# sheet.net
KiCad netlist of a schematic drawn in EAGLE
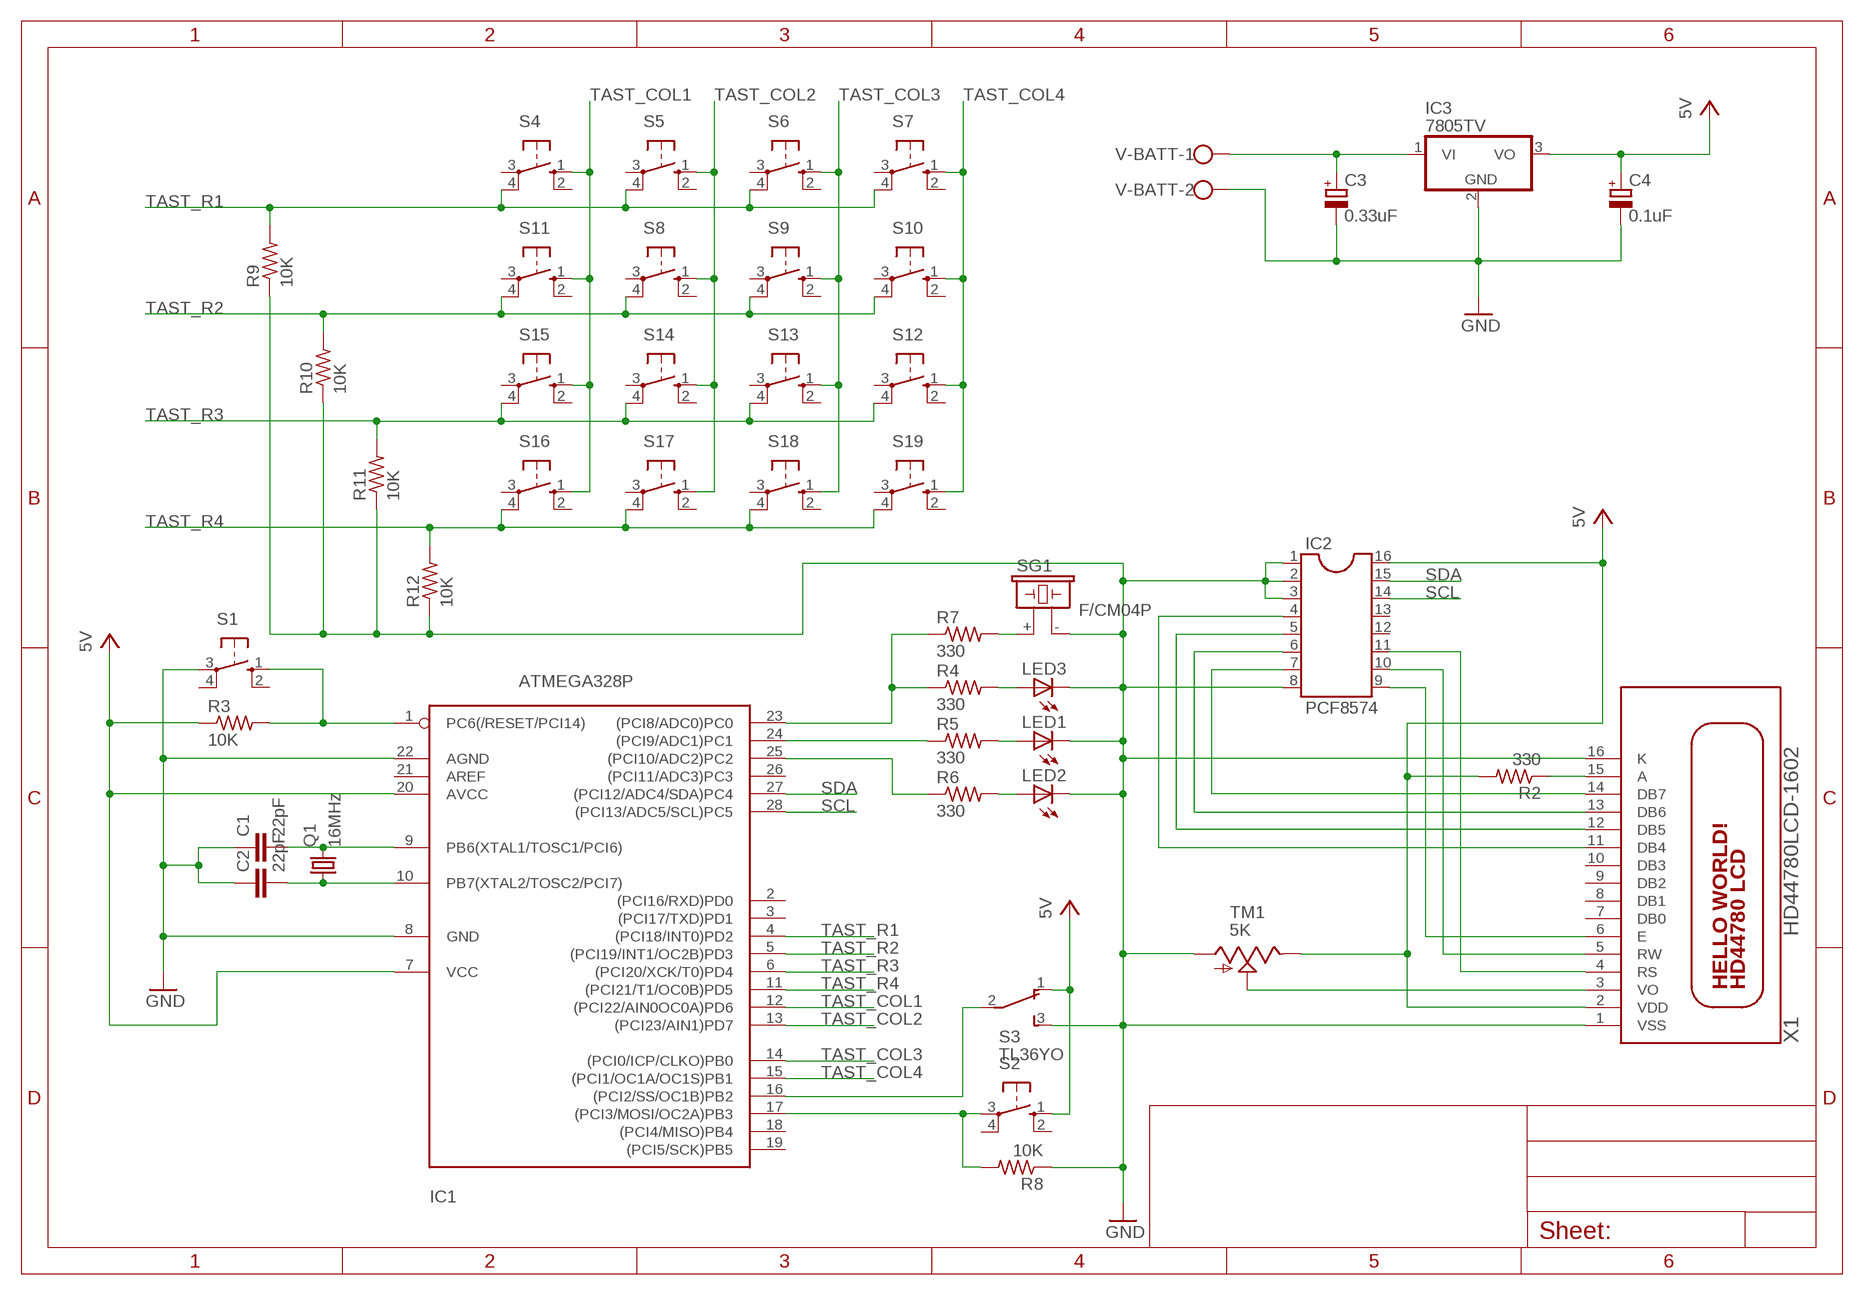
[diagram p0: schematic, sheet 1]

(export (version "E")
  (design (tool "Eeschema 10.0.6"))
  (components
    (comp (ref "C1")
      (value "22pF")
      (footprint "eagle-import:C025-024X044")
      (libsource (lib "eagle-import") (part "C-EU025-024X044"))
    )
    (comp (ref "C2")
      (value "22pF")
      (footprint "eagle-import:C025-024X044")
      (libsource (lib "eagle-import") (part "C-EU025-024X044"))
    )
    (comp (ref "C3")
      (value "0.33uF")
      (footprint "eagle-import:E5-6")
      (libsource (lib "eagle-import") (part "CPOL-EUE5-6"))
    )
    (comp (ref "C4")
      (value "0.1uF")
      (footprint "eagle-import:E5-6")
      (libsource (lib "eagle-import") (part "CPOL-EUE5-6"))
    )
    (comp (ref "FRAME1")
      (value "A4L-LOC")
      (footprint "eagle-import:A4L-LOC")
      (fields
        (field (name "DATE") "23/03/2015")
        (field (name "PAGES") "1/1")
        (field (name "REV") "V1.0")
        (field (name "SHEET_NAME") "Soft Bomb")
      )
      (libsource (lib "eagle-import") (part "A4L-LOC"))
    )
    (comp (ref "IC1")
      (value "ATMEGA328P")
      (footprint "eagle-import:DIL28-3")
      (libsource (lib "eagle-import") (part "ATMEGA168P-20"))
    )
    (comp (ref "IC2")
      (value "PCF8574")
      (footprint "eagle-import:DIL16")
      (libsource (lib "eagle-import") (part "DIL16"))
    )
    (comp (ref "IC3")
      (value "7805TV")
      (footprint "eagle-import:TO220V")
      (libsource (lib "eagle-import") (part "78TV05"))
    )
    (comp (ref "LED1")
      (value "LED5MM")
      (footprint "eagle-import:LED5MM")
      (libsource (lib "eagle-import") (part "LED5MM"))
    )
    (comp (ref "LED2")
      (value "LED3MM")
      (footprint "eagle-import:LED3MM")
      (libsource (lib "eagle-import") (part "LED3MM"))
    )
    (comp (ref "LED3")
      (value "LED3MM")
      (footprint "eagle-import:LED3MM")
      (libsource (lib "eagle-import") (part "LED3MM"))
    )
    (comp (ref "Q1")
      (value "16MHz")
      (footprint "eagle-import:HC49_S")
      (libsource (lib "eagle-import") (part "CRYSTALHC49S"))
    )
    (comp (ref "R2")
      (value "330")
      (footprint "eagle-import:0204_7")
      (libsource (lib "eagle-import") (part "R-US_0204/7"))
    )
    (comp (ref "R3")
      (value "10K")
      (footprint "eagle-import:0207_12")
      (libsource (lib "eagle-import") (part "resistor_R-US_0207/12"))
    )
    (comp (ref "R4")
      (value "330")
      (footprint "eagle-import:0207_12")
      (libsource (lib "eagle-import") (part "resistor_R-US_0207/12"))
    )
    (comp (ref "R5")
      (value "330")
      (footprint "eagle-import:0207_12")
      (libsource (lib "eagle-import") (part "resistor_R-US_0207/12"))
    )
    (comp (ref "R6")
      (value "330")
      (footprint "eagle-import:0207_12")
      (libsource (lib "eagle-import") (part "resistor_R-US_0207/12"))
    )
    (comp (ref "R7")
      (value "330")
      (footprint "eagle-import:0207_12")
      (libsource (lib "eagle-import") (part "resistor_R-US_0207/12"))
    )
    (comp (ref "R8")
      (value "10K")
      (footprint "eagle-import:0207_12")
      (libsource (lib "eagle-import") (part "resistor_R-US_0207/12"))
    )
    (comp (ref "R9")
      (value "10K")
      (footprint "eagle-import:0207_12")
      (libsource (lib "eagle-import") (part "resistor_R-US_0207/12"))
    )
    (comp (ref "R10")
      (value "10K")
      (footprint "eagle-import:0207_12")
      (libsource (lib "eagle-import") (part "resistor_R-US_0207/12"))
    )
    (comp (ref "R11")
      (value "10K")
      (footprint "eagle-import:0207_12")
      (libsource (lib "eagle-import") (part "resistor_R-US_0207/12"))
    )
    (comp (ref "R12")
      (value "10K")
      (footprint "eagle-import:0207_12")
      (libsource (lib "eagle-import") (part "resistor_R-US_0207/12"))
    )
    (comp (ref "S1")
      (value "40-XX")
      (footprint "eagle-import:B3F-40XX")
      (fields (field (name "MF") "OMRON COMPONENTS USA") (field (name "MPN") "B3F-4000"))
      (libsource (lib "eagle-import") (part "40-XX"))
    )
    (comp (ref "S2")
      (value "40-XX")
      (footprint "eagle-import:B3F-40XX")
      (fields (field (name "MF") "OMRON COMPONENTS USA") (field (name "MPN") "B3F-4000"))
      (libsource (lib "eagle-import") (part "40-XX"))
    )
    (comp (ref "S3")
      (value "TL36YO")
      (footprint "eagle-import:TL3XYO")
      (libsource (lib "eagle-import") (part "TL36YO"))
    )
    (comp (ref "S4")
      (value "40-XX")
      (footprint "eagle-import:B3F-40XX")
      (fields (field (name "MF") "OMRON COMPONENTS USA") (field (name "MPN") "B3F-4000"))
      (libsource (lib "eagle-import") (part "40-XX"))
    )
    (comp (ref "S5")
      (value "40-XX")
      (footprint "eagle-import:B3F-40XX")
      (fields (field (name "MF") "OMRON COMPONENTS USA") (field (name "MPN") "B3F-4000"))
      (libsource (lib "eagle-import") (part "40-XX"))
    )
    (comp (ref "S6")
      (value "40-XX")
      (footprint "eagle-import:B3F-40XX")
      (fields (field (name "MF") "OMRON COMPONENTS USA") (field (name "MPN") "B3F-4000"))
      (libsource (lib "eagle-import") (part "40-XX"))
    )
    (comp (ref "S7")
      (value "40-XX")
      (footprint "eagle-import:B3F-40XX")
      (fields (field (name "MF") "OMRON COMPONENTS USA") (field (name "MPN") "B3F-4000"))
      (libsource (lib "eagle-import") (part "40-XX"))
    )
    (comp (ref "S8")
      (value "40-XX")
      (footprint "eagle-import:B3F-40XX")
      (fields (field (name "MF") "OMRON COMPONENTS USA") (field (name "MPN") "B3F-4000"))
      (libsource (lib "eagle-import") (part "40-XX"))
    )
    (comp (ref "S9")
      (value "40-XX")
      (footprint "eagle-import:B3F-40XX")
      (fields (field (name "MF") "OMRON COMPONENTS USA") (field (name "MPN") "B3F-4000"))
      (libsource (lib "eagle-import") (part "40-XX"))
    )
    (comp (ref "S10")
      (value "40-XX")
      (footprint "eagle-import:B3F-40XX")
      (fields (field (name "MF") "OMRON COMPONENTS USA") (field (name "MPN") "B3F-4000"))
      (libsource (lib "eagle-import") (part "40-XX"))
    )
    (comp (ref "S11")
      (value "40-XX")
      (footprint "eagle-import:B3F-40XX")
      (fields (field (name "MF") "OMRON COMPONENTS USA") (field (name "MPN") "B3F-4000"))
      (libsource (lib "eagle-import") (part "40-XX"))
    )
    (comp (ref "S12")
      (value "40-XX")
      (footprint "eagle-import:B3F-40XX")
      (fields (field (name "MF") "OMRON COMPONENTS USA") (field (name "MPN") "B3F-4000"))
      (libsource (lib "eagle-import") (part "40-XX"))
    )
    (comp (ref "S13")
      (value "40-XX")
      (footprint "eagle-import:B3F-40XX")
      (fields (field (name "MF") "OMRON COMPONENTS USA") (field (name "MPN") "B3F-4000"))
      (libsource (lib "eagle-import") (part "40-XX"))
    )
    (comp (ref "S14")
      (value "40-XX")
      (footprint "eagle-import:B3F-40XX")
      (fields (field (name "MF") "OMRON COMPONENTS USA") (field (name "MPN") "B3F-4000"))
      (libsource (lib "eagle-import") (part "40-XX"))
    )
    (comp (ref "S15")
      (value "40-XX")
      (footprint "eagle-import:B3F-40XX")
      (fields (field (name "MF") "OMRON COMPONENTS USA") (field (name "MPN") "B3F-4000"))
      (libsource (lib "eagle-import") (part "40-XX"))
    )
    (comp (ref "S16")
      (value "40-XX")
      (footprint "eagle-import:B3F-40XX")
      (fields (field (name "MF") "OMRON COMPONENTS USA") (field (name "MPN") "B3F-4000"))
      (libsource (lib "eagle-import") (part "40-XX"))
    )
    (comp (ref "S17")
      (value "40-XX")
      (footprint "eagle-import:B3F-40XX")
      (fields (field (name "MF") "OMRON COMPONENTS USA") (field (name "MPN") "B3F-4000"))
      (libsource (lib "eagle-import") (part "40-XX"))
    )
    (comp (ref "S18")
      (value "40-XX")
      (footprint "eagle-import:B3F-40XX")
      (fields (field (name "MF") "OMRON COMPONENTS USA") (field (name "MPN") "B3F-4000"))
      (libsource (lib "eagle-import") (part "40-XX"))
    )
    (comp (ref "S19")
      (value "40-XX")
      (footprint "eagle-import:B3F-40XX")
      (fields (field (name "MF") "OMRON COMPONENTS USA") (field (name "MPN") "B3F-4000"))
      (libsource (lib "eagle-import") (part "40-XX"))
    )
    (comp (ref "SG1")
      (value "F/CM04P")
      (footprint "eagle-import:F_CM04P")
      (libsource (lib "eagle-import") (part "F/CM04P"))
    )
    (comp (ref "TM1")
      (value "5K")
      (footprint "eagle-import:6MM")
      (libsource (lib "eagle-import") (part "TRIM"))
    )
    (comp (ref "V-BATT")
      (value "W237-102")
      (footprint "eagle-import:W237-102")
      (fields (field (name "MPN") "237-102"))
      (libsource (lib "eagle-import") (part "W237-102"))
    )
    (comp (ref "X1")
      (value "HD44780LCD-1602")
      (footprint "eagle-import:LCD1602")
      (libsource (lib "eagle-import") (part "HD44780LCD-1602"))
    )
  )
  (nets
    (net (code "1") (name "/SCL") (class "Default")
      (node (ref "IC1") (pin "28") (pinfunction "(PCI13/ADC5/SCL)PC5_28") (pintype "bidirectional"))
      (node (ref "IC2") (pin "14") (pinfunction "14_14") (pintype "passive"))
    )
    (net (code "2") (name "/SDA") (class "Default")
      (node (ref "IC1") (pin "27") (pinfunction "(PCI12/ADC4/SDA)PC4_27") (pintype "bidirectional"))
      (node (ref "IC2") (pin "15") (pinfunction "15_15") (pintype "passive"))
    )
    (net (code "3") (name "/TAST_COL1") (class "Default")
      (node (ref "IC1") (pin "12") (pinfunction "(PCI22/AIN0OC0A)PD6_12") (pintype "bidirectional"))
      (node (ref "S11") (pin "1") (pinfunction "S_1") (pintype "passive"))
      (node (ref "S15") (pin "1") (pinfunction "S_1") (pintype "passive"))
      (node (ref "S16") (pin "1") (pinfunction "S_1") (pintype "passive"))
      (node (ref "S4") (pin "1") (pinfunction "S_1") (pintype "passive"))
    )
    (net (code "4") (name "/TAST_COL2") (class "Default")
      (node (ref "IC1") (pin "13") (pinfunction "(PCI23/AIN1)PD7_13") (pintype "bidirectional"))
      (node (ref "S14") (pin "1") (pinfunction "S_1") (pintype "passive"))
      (node (ref "S17") (pin "1") (pinfunction "S_1") (pintype "passive"))
      (node (ref "S5") (pin "1") (pinfunction "S_1") (pintype "passive"))
      (node (ref "S8") (pin "1") (pinfunction "S_1") (pintype "passive"))
    )
    (net (code "5") (name "/TAST_COL3") (class "Default")
      (node (ref "IC1") (pin "14") (pinfunction "(PCI0/ICP/CLKO)PB0_14") (pintype "bidirectional"))
      (node (ref "S13") (pin "1") (pinfunction "S_1") (pintype "passive"))
      (node (ref "S18") (pin "1") (pinfunction "S_1") (pintype "passive"))
      (node (ref "S6") (pin "1") (pinfunction "S_1") (pintype "passive"))
      (node (ref "S9") (pin "1") (pinfunction "S_1") (pintype "passive"))
    )
    (net (code "6") (name "/TAST_COL4") (class "Default")
      (node (ref "IC1") (pin "15") (pinfunction "(PCI1/OC1A/OC1S)PB1_15") (pintype "bidirectional"))
      (node (ref "S10") (pin "1") (pinfunction "S_1") (pintype "passive"))
      (node (ref "S12") (pin "1") (pinfunction "S_1") (pintype "passive"))
      (node (ref "S19") (pin "1") (pinfunction "S_1") (pintype "passive"))
      (node (ref "S7") (pin "1") (pinfunction "S_1") (pintype "passive"))
    )
    (net (code "7") (name "/TAST_R1") (class "Default")
      (node (ref "IC1") (pin "4") (pinfunction "(PCI18/INT0)PD2_4") (pintype "bidirectional"))
      (node (ref "R9") (pin "2") (pinfunction "2_2") (pintype "passive"))
      (node (ref "S4") (pin "4") (pinfunction "P1_4") (pintype "passive"))
      (node (ref "S5") (pin "4") (pinfunction "P1_4") (pintype "passive"))
      (node (ref "S6") (pin "4") (pinfunction "P1_4") (pintype "passive"))
      (node (ref "S7") (pin "4") (pinfunction "P1_4") (pintype "passive"))
    )
    (net (code "8") (name "/TAST_R2") (class "Default")
      (node (ref "IC1") (pin "5") (pinfunction "(PCI19/INT1/OC2B)PD3_5") (pintype "bidirectional"))
      (node (ref "R10") (pin "2") (pinfunction "2_2") (pintype "passive"))
      (node (ref "S10") (pin "4") (pinfunction "P1_4") (pintype "passive"))
      (node (ref "S11") (pin "4") (pinfunction "P1_4") (pintype "passive"))
      (node (ref "S8") (pin "4") (pinfunction "P1_4") (pintype "passive"))
      (node (ref "S9") (pin "4") (pinfunction "P1_4") (pintype "passive"))
    )
    (net (code "9") (name "/TAST_R3") (class "Default")
      (node (ref "IC1") (pin "6") (pinfunction "(PCI20/XCK/T0)PD4_6") (pintype "bidirectional"))
      (node (ref "R11") (pin "2") (pinfunction "2_2") (pintype "passive"))
      (node (ref "S12") (pin "4") (pinfunction "P1_4") (pintype "passive"))
      (node (ref "S13") (pin "4") (pinfunction "P1_4") (pintype "passive"))
      (node (ref "S14") (pin "4") (pinfunction "P1_4") (pintype "passive"))
      (node (ref "S15") (pin "4") (pinfunction "P1_4") (pintype "passive"))
    )
    (net (code "10") (name "/TAST_R4") (class "Default")
      (node (ref "IC1") (pin "11") (pinfunction "(PCI21/T1/OC0B)PD5_11") (pintype "bidirectional"))
      (node (ref "R12") (pin "2") (pinfunction "2_2") (pintype "passive"))
      (node (ref "S16") (pin "4") (pinfunction "P1_4") (pintype "passive"))
      (node (ref "S17") (pin "4") (pinfunction "P1_4") (pintype "passive"))
      (node (ref "S18") (pin "4") (pinfunction "P1_4") (pintype "passive"))
      (node (ref "S19") (pin "4") (pinfunction "P1_4") (pintype "passive"))
    )
    (net (code "11") (name "5V") (class "Default")
      (node (ref "C4") (pin "+") (pinfunction "+_+") (pintype "passive"))
      (node (ref "IC1") (pin "20") (pinfunction "AVCC_20") (pintype "bidirectional"))
      (node (ref "IC1") (pin "7") (pinfunction "VCC_7") (pintype "bidirectional"))
      (node (ref "IC2") (pin "16") (pinfunction "16_16") (pintype "passive"))
      (node (ref "IC3") (pin "3") (pinfunction "VO_3") (pintype "passive"))
      (node (ref "R2") (pin "2") (pinfunction "2_2") (pintype "passive"))
      (node (ref "R3") (pin "1") (pinfunction "1_1") (pintype "passive"))
      (node (ref "S2") (pin "1") (pinfunction "S_1") (pintype "passive"))
      (node (ref "S3") (pin "1") (pinfunction "O_1") (pintype "passive"))
      (node (ref "TM1") (pin "E") (pinfunction "E_E") (pintype "passive"))
      (node (ref "X1") (pin "2") (pinfunction "VDD_2") (pintype "power_in"))
    )
    (net (code "12") (name "GND") (class "Default")
      (node (ref "C1") (pin "1") (pinfunction "1_1") (pintype "passive"))
      (node (ref "C2") (pin "1") (pinfunction "1_1") (pintype "passive"))
      (node (ref "C3") (pin "-") (pinfunction "-_-") (pintype "passive"))
      (node (ref "C4") (pin "-") (pinfunction "-_-") (pintype "passive"))
      (node (ref "IC1") (pin "22") (pinfunction "AGND_22") (pintype "bidirectional"))
      (node (ref "IC1") (pin "8") (pinfunction "GND_8") (pintype "bidirectional"))
      (node (ref "IC2") (pin "1") (pinfunction "1_1") (pintype "passive"))
      (node (ref "IC2") (pin "2") (pinfunction "2_2") (pintype "passive"))
      (node (ref "IC2") (pin "3") (pinfunction "3_3") (pintype "passive"))
      (node (ref "IC2") (pin "8") (pinfunction "8_8") (pintype "passive"))
      (node (ref "IC3") (pin "2") (pinfunction "GND_2") (pintype "passive"))
      (node (ref "LED1") (pin "K") (pinfunction "C_K") (pintype "passive"))
      (node (ref "LED2") (pin "K") (pinfunction "C_K") (pintype "passive"))
      (node (ref "LED3") (pin "K") (pinfunction "C_K") (pintype "passive"))
      (node (ref "R10") (pin "1") (pinfunction "1_1") (pintype "passive"))
      (node (ref "R11") (pin "1") (pinfunction "1_1") (pintype "passive"))
      (node (ref "R12") (pin "1") (pinfunction "1_1") (pintype "passive"))
      (node (ref "R8") (pin "1") (pinfunction "1_1") (pintype "passive"))
      (node (ref "R9") (pin "1") (pinfunction "1_1") (pintype "passive"))
      (node (ref "S1") (pin "3") (pinfunction "P_3") (pintype "passive"))
      (node (ref "S3") (pin "3") (pinfunction "S_3") (pintype "passive"))
      (node (ref "SG1") (pin "-") (pinfunction "2_-") (pintype "passive"))
      (node (ref "TM1") (pin "A") (pinfunction "A_A") (pintype "passive"))
      (node (ref "V-BATT") (pin "2") (pinfunction "KL_2") (pintype "passive"))
      (node (ref "X1") (pin "1") (pinfunction "VSS_1") (pintype "power_in"))
      (node (ref "X1") (pin "16") (pinfunction "K_16") (pintype "input"))
    )
    (net (code "13") (name "Net-(IC1-(PCI2{slash}SS{slash}OC1B)PB2)") (class "Default")
      (node (ref "IC1") (pin "16") (pinfunction "(PCI2/SS/OC1B)PB2_16") (pintype "bidirectional"))
      (node (ref "S3") (pin "2") (pinfunction "P_2") (pintype "passive"))
    )
    (net (code "14") (name "Net-(IC1-(PCI3{slash}MOSI{slash}OC2A)PB3)") (class "Default")
      (node (ref "IC1") (pin "17") (pinfunction "(PCI3/MOSI/OC2A)PB3_17") (pintype "bidirectional"))
      (node (ref "R8") (pin "2") (pinfunction "2_2") (pintype "passive"))
      (node (ref "S2") (pin "3") (pinfunction "P_3") (pintype "passive"))
    )
    (net (code "15") (name "Net-(IC1-(PCI8{slash}ADC0)PC0)") (class "Default")
      (node (ref "IC1") (pin "23") (pinfunction "(PCI8/ADC0)PC0_23") (pintype "bidirectional"))
      (node (ref "R4") (pin "1") (pinfunction "1_1") (pintype "passive"))
      (node (ref "R7") (pin "1") (pinfunction "1_1") (pintype "passive"))
    )
    (net (code "16") (name "Net-(IC1-(PCI9{slash}ADC1)PC1)") (class "Default")
      (node (ref "IC1") (pin "24") (pinfunction "(PCI9/ADC1)PC1_24") (pintype "bidirectional"))
      (node (ref "R5") (pin "1") (pinfunction "1_1") (pintype "passive"))
    )
    (net (code "17") (name "Net-(IC1-(PCI10{slash}ADC2)PC2)") (class "Default")
      (node (ref "IC1") (pin "25") (pinfunction "(PCI10/ADC2)PC2_25") (pintype "bidirectional"))
      (node (ref "R6") (pin "1") (pinfunction "1_1") (pintype "passive"))
    )
    (net (code "18") (name "Net-(IC1-PB6(XTAL1{slash}TOSC1{slash}PCI6))") (class "Default")
      (node (ref "C1") (pin "2") (pinfunction "2_2") (pintype "passive"))
      (node (ref "IC1") (pin "9") (pinfunction "PB6(XTAL1/TOSC1/PCI6)_9") (pintype "bidirectional"))
      (node (ref "Q1") (pin "2") (pinfunction "2_2") (pintype "passive"))
    )
    (net (code "19") (name "Net-(IC1-PB7(XTAL2{slash}TOSC2{slash}PCI7))") (class "Default")
      (node (ref "C2") (pin "2") (pinfunction "2_2") (pintype "passive"))
      (node (ref "IC1") (pin "10") (pinfunction "PB7(XTAL2/TOSC2/PCI7)_10") (pintype "bidirectional"))
      (node (ref "Q1") (pin "1") (pinfunction "1_1") (pintype "passive"))
    )
    (net (code "20") (name "Net-(IC1-PC6({slash}RESET{slash}PCI14))") (class "Default")
      (node (ref "IC1") (pin "1") (pinfunction "PC6(/RESET/PCI14)_1") (pintype "bidirectional"))
      (node (ref "R3") (pin "2") (pinfunction "2_2") (pintype "passive"))
      (node (ref "S1") (pin "1") (pinfunction "S_1") (pintype "passive"))
    )
    (net (code "21") (name "Net-(IC3-VI)") (class "Default")
      (node (ref "C3") (pin "+") (pinfunction "+_+") (pintype "passive"))
      (node (ref "IC3") (pin "1") (pinfunction "VI_1") (pintype "input"))
      (node (ref "V-BATT") (pin "1") (pinfunction "KL_1") (pintype "passive"))
    )
    (net (code "22") (name "Net-(LED1-PadA)") (class "Default")
      (node (ref "LED1") (pin "A") (pinfunction "A_A") (pintype "passive"))
      (node (ref "R5") (pin "2") (pinfunction "2_2") (pintype "passive"))
    )
    (net (code "23") (name "Net-(LED2-PadA)") (class "Default")
      (node (ref "LED2") (pin "A") (pinfunction "A_A") (pintype "passive"))
      (node (ref "R6") (pin "2") (pinfunction "2_2") (pintype "passive"))
    )
    (net (code "24") (name "Net-(LED3-PadA)") (class "Default")
      (node (ref "LED3") (pin "A") (pinfunction "A_A") (pintype "passive"))
      (node (ref "R4") (pin "2") (pinfunction "2_2") (pintype "passive"))
    )
    (net (code "25") (name "Net-(SG1-1)") (class "Default")
      (node (ref "R7") (pin "2") (pinfunction "2_2") (pintype "passive"))
      (node (ref "SG1") (pin "+") (pinfunction "1_+") (pintype "passive"))
    )
    (net (code "26") (name "Net-(X1-A)") (class "Default")
      (node (ref "R2") (pin "1") (pinfunction "1_1") (pintype "passive"))
      (node (ref "X1") (pin "15") (pinfunction "A_15") (pintype "input"))
    )
    (net (code "27") (name "Net-(X1-DB4)") (class "Default")
      (node (ref "IC2") (pin "4") (pinfunction "4_4") (pintype "passive"))
      (node (ref "X1") (pin "11") (pinfunction "DB4_11") (pintype "bidirectional"))
    )
    (net (code "28") (name "Net-(X1-DB5)") (class "Default")
      (node (ref "IC2") (pin "5") (pinfunction "5_5") (pintype "passive"))
      (node (ref "X1") (pin "12") (pinfunction "DB5_12") (pintype "bidirectional"))
    )
    (net (code "29") (name "Net-(X1-DB6)") (class "Default")
      (node (ref "IC2") (pin "6") (pinfunction "6_6") (pintype "passive"))
      (node (ref "X1") (pin "13") (pinfunction "DB6_13") (pintype "bidirectional"))
    )
    (net (code "30") (name "Net-(X1-DB7)") (class "Default")
      (node (ref "IC2") (pin "7") (pinfunction "7_7") (pintype "passive"))
      (node (ref "X1") (pin "14") (pinfunction "DB7_14") (pintype "bidirectional"))
    )
    (net (code "31") (name "Net-(X1-E)") (class "Default")
      (node (ref "IC2") (pin "9") (pinfunction "9_9") (pintype "passive"))
      (node (ref "X1") (pin "6") (pinfunction "E_6") (pintype "input"))
    )
    (net (code "32") (name "Net-(X1-RS)") (class "Default")
      (node (ref "IC2") (pin "11") (pinfunction "11_11") (pintype "passive"))
      (node (ref "X1") (pin "4") (pinfunction "RS_4") (pintype "input"))
    )
    (net (code "33") (name "Net-(X1-RW)") (class "Default")
      (node (ref "IC2") (pin "10") (pinfunction "10_10") (pintype "passive"))
      (node (ref "X1") (pin "5") (pinfunction "RW_5") (pintype "input"))
    )
    (net (code "34") (name "Net-(X1-VO)") (class "Default")
      (node (ref "TM1") (pin "S") (pinfunction "S_S") (pintype "passive"))
      (node (ref "X1") (pin "3") (pinfunction "VO_3") (pintype "input"))
    )
    (net (code "35") (name "unconnected-(IC1-(PCI4{slash}MISO)PB4-Pad18)") (class "Default")
      (node (ref "IC1") (pin "18") (pinfunction "(PCI4/MISO)PB4_18") (pintype "bidirectional"))
    )
    (net (code "36") (name "unconnected-(IC1-(PCI5{slash}SCK)PB5-Pad19)") (class "Default")
      (node (ref "IC1") (pin "19") (pinfunction "(PCI5/SCK)PB5_19") (pintype "bidirectional"))
    )
    (net (code "37") (name "unconnected-(IC1-(PCI11{slash}ADC3)PC3-Pad26)") (class "Default")
      (node (ref "IC1") (pin "26") (pinfunction "(PCI11/ADC3)PC3_26") (pintype "bidirectional"))
    )
    (net (code "38") (name "unconnected-(IC1-(PCI16{slash}RXD)PD0-Pad2)") (class "Default")
      (node (ref "IC1") (pin "2") (pinfunction "(PCI16/RXD)PD0_2") (pintype "bidirectional"))
    )
    (net (code "39") (name "unconnected-(IC1-(PCI17{slash}TXD)PD1-Pad3)") (class "Default")
      (node (ref "IC1") (pin "3") (pinfunction "(PCI17/TXD)PD1_3") (pintype "bidirectional"))
    )
    (net (code "40") (name "unconnected-(IC1-AREF-Pad21)") (class "Default")
      (node (ref "IC1") (pin "21") (pinfunction "AREF_21") (pintype "bidirectional"))
    )
    (net (code "41") (name "unconnected-(IC2-Pad12)") (class "Default")
      (node (ref "IC2") (pin "12") (pinfunction "12_12") (pintype "passive"))
    )
    (net (code "42") (name "unconnected-(IC2-Pad13)") (class "Default")
      (node (ref "IC2") (pin "13") (pinfunction "13_13") (pintype "passive"))
    )
    (net (code "43") (name "unconnected-(S1-P1-Pad4)") (class "Default")
      (node (ref "S1") (pin "4") (pinfunction "P1_4") (pintype "passive"))
    )
    (net (code "44") (name "unconnected-(S1-S1-Pad2)") (class "Default")
      (node (ref "S1") (pin "2") (pinfunction "S1_2") (pintype "passive"))
    )
    (net (code "45") (name "unconnected-(S2-P1-Pad4)") (class "Default")
      (node (ref "S2") (pin "4") (pinfunction "P1_4") (pintype "passive"))
    )
    (net (code "46") (name "unconnected-(S2-S1-Pad2)") (class "Default")
      (node (ref "S2") (pin "2") (pinfunction "S1_2") (pintype "passive"))
    )
    (net (code "47") (name "unconnected-(S4-P-Pad3)") (class "Default")
      (node (ref "S4") (pin "3") (pinfunction "P_3") (pintype "passive"))
    )
    (net (code "48") (name "unconnected-(S4-S1-Pad2)") (class "Default")
      (node (ref "S4") (pin "2") (pinfunction "S1_2") (pintype "passive"))
    )
    (net (code "49") (name "unconnected-(S5-P-Pad3)") (class "Default")
      (node (ref "S5") (pin "3") (pinfunction "P_3") (pintype "passive"))
    )
    (net (code "50") (name "unconnected-(S5-S1-Pad2)") (class "Default")
      (node (ref "S5") (pin "2") (pinfunction "S1_2") (pintype "passive"))
    )
    (net (code "51") (name "unconnected-(S6-P-Pad3)") (class "Default")
      (node (ref "S6") (pin "3") (pinfunction "P_3") (pintype "passive"))
    )
    (net (code "52") (name "unconnected-(S6-S1-Pad2)") (class "Default")
      (node (ref "S6") (pin "2") (pinfunction "S1_2") (pintype "passive"))
    )
    (net (code "53") (name "unconnected-(S7-P-Pad3)") (class "Default")
      (node (ref "S7") (pin "3") (pinfunction "P_3") (pintype "passive"))
    )
    (net (code "54") (name "unconnected-(S7-S1-Pad2)") (class "Default")
      (node (ref "S7") (pin "2") (pinfunction "S1_2") (pintype "passive"))
    )
    (net (code "55") (name "unconnected-(S8-P-Pad3)") (class "Default")
      (node (ref "S8") (pin "3") (pinfunction "P_3") (pintype "passive"))
    )
    (net (code "56") (name "unconnected-(S8-S1-Pad2)") (class "Default")
      (node (ref "S8") (pin "2") (pinfunction "S1_2") (pintype "passive"))
    )
    (net (code "57") (name "unconnected-(S9-P-Pad3)") (class "Default")
      (node (ref "S9") (pin "3") (pinfunction "P_3") (pintype "passive"))
    )
    (net (code "58") (name "unconnected-(S9-S1-Pad2)") (class "Default")
      (node (ref "S9") (pin "2") (pinfunction "S1_2") (pintype "passive"))
    )
    (net (code "59") (name "unconnected-(S10-P-Pad3)") (class "Default")
      (node (ref "S10") (pin "3") (pinfunction "P_3") (pintype "passive"))
    )
    (net (code "60") (name "unconnected-(S10-S1-Pad2)") (class "Default")
      (node (ref "S10") (pin "2") (pinfunction "S1_2") (pintype "passive"))
    )
    (net (code "61") (name "unconnected-(S11-P-Pad3)") (class "Default")
      (node (ref "S11") (pin "3") (pinfunction "P_3") (pintype "passive"))
    )
    (net (code "62") (name "unconnected-(S11-S1-Pad2)") (class "Default")
      (node (ref "S11") (pin "2") (pinfunction "S1_2") (pintype "passive"))
    )
    (net (code "63") (name "unconnected-(S12-P-Pad3)") (class "Default")
      (node (ref "S12") (pin "3") (pinfunction "P_3") (pintype "passive"))
    )
    (net (code "64") (name "unconnected-(S12-S1-Pad2)") (class "Default")
      (node (ref "S12") (pin "2") (pinfunction "S1_2") (pintype "passive"))
    )
    (net (code "65") (name "unconnected-(S13-P-Pad3)") (class "Default")
      (node (ref "S13") (pin "3") (pinfunction "P_3") (pintype "passive"))
    )
    (net (code "66") (name "unconnected-(S13-S1-Pad2)") (class "Default")
      (node (ref "S13") (pin "2") (pinfunction "S1_2") (pintype "passive"))
    )
    (net (code "67") (name "unconnected-(S14-P-Pad3)") (class "Default")
      (node (ref "S14") (pin "3") (pinfunction "P_3") (pintype "passive"))
    )
    (net (code "68") (name "unconnected-(S14-S1-Pad2)") (class "Default")
      (node (ref "S14") (pin "2") (pinfunction "S1_2") (pintype "passive"))
    )
    (net (code "69") (name "unconnected-(S15-P-Pad3)") (class "Default")
      (node (ref "S15") (pin "3") (pinfunction "P_3") (pintype "passive"))
    )
    (net (code "70") (name "unconnected-(S15-S1-Pad2)") (class "Default")
      (node (ref "S15") (pin "2") (pinfunction "S1_2") (pintype "passive"))
    )
    (net (code "71") (name "unconnected-(S16-P-Pad3)") (class "Default")
      (node (ref "S16") (pin "3") (pinfunction "P_3") (pintype "passive"))
    )
    (net (code "72") (name "unconnected-(S16-S1-Pad2)") (class "Default")
      (node (ref "S16") (pin "2") (pinfunction "S1_2") (pintype "passive"))
    )
    (net (code "73") (name "unconnected-(S17-P-Pad3)") (class "Default")
      (node (ref "S17") (pin "3") (pinfunction "P_3") (pintype "passive"))
    )
    (net (code "74") (name "unconnected-(S17-S1-Pad2)") (class "Default")
      (node (ref "S17") (pin "2") (pinfunction "S1_2") (pintype "passive"))
    )
    (net (code "75") (name "unconnected-(S18-P-Pad3)") (class "Default")
      (node (ref "S18") (pin "3") (pinfunction "P_3") (pintype "passive"))
    )
    (net (code "76") (name "unconnected-(S18-S1-Pad2)") (class "Default")
      (node (ref "S18") (pin "2") (pinfunction "S1_2") (pintype "passive"))
    )
    (net (code "77") (name "unconnected-(S19-P-Pad3)") (class "Default")
      (node (ref "S19") (pin "3") (pinfunction "P_3") (pintype "passive"))
    )
    (net (code "78") (name "unconnected-(S19-S1-Pad2)") (class "Default")
      (node (ref "S19") (pin "2") (pinfunction "S1_2") (pintype "passive"))
    )
    (net (code "79") (name "unconnected-(X1-DB0-Pad7)") (class "Default")
      (node (ref "X1") (pin "7") (pinfunction "DB0_7") (pintype "bidirectional"))
    )
    (net (code "80") (name "unconnected-(X1-DB1-Pad8)") (class "Default")
      (node (ref "X1") (pin "8") (pinfunction "DB1_8") (pintype "bidirectional"))
    )
    (net (code "81") (name "unconnected-(X1-DB2-Pad9)") (class "Default")
      (node (ref "X1") (pin "9") (pinfunction "DB2_9") (pintype "bidirectional"))
    )
    (net (code "82") (name "unconnected-(X1-DB3-Pad10)") (class "Default")
      (node (ref "X1") (pin "10") (pinfunction "DB3_10") (pintype "bidirectional"))
    )
  )
)
